# MotionBoard_Rev_C.net
KiCad netlist of a schematic drawn in EAGLE
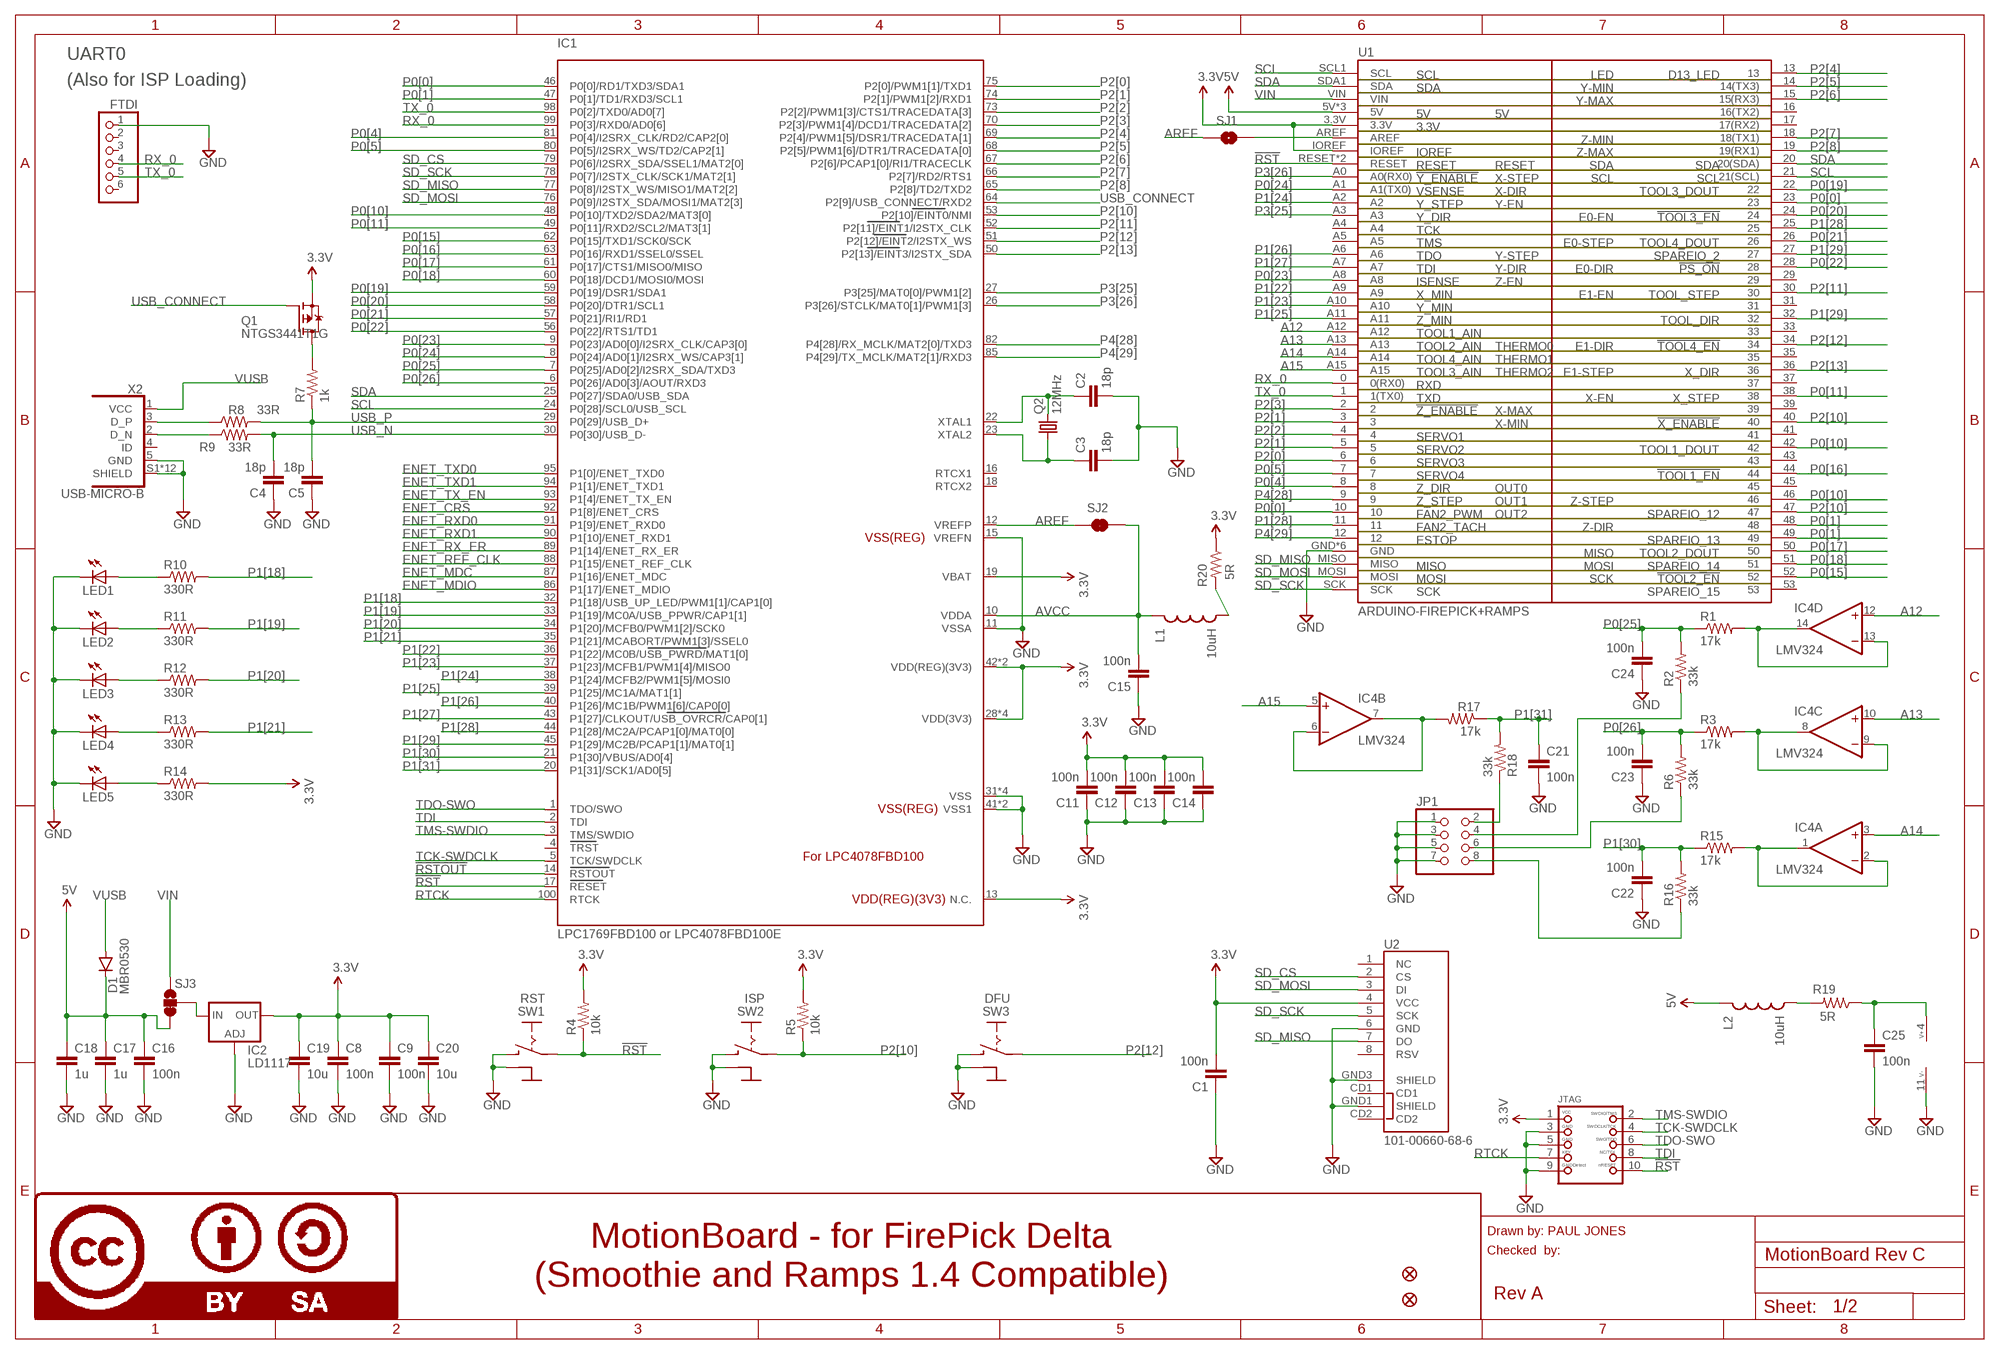
[diagram p0: schematic, sheet 1]
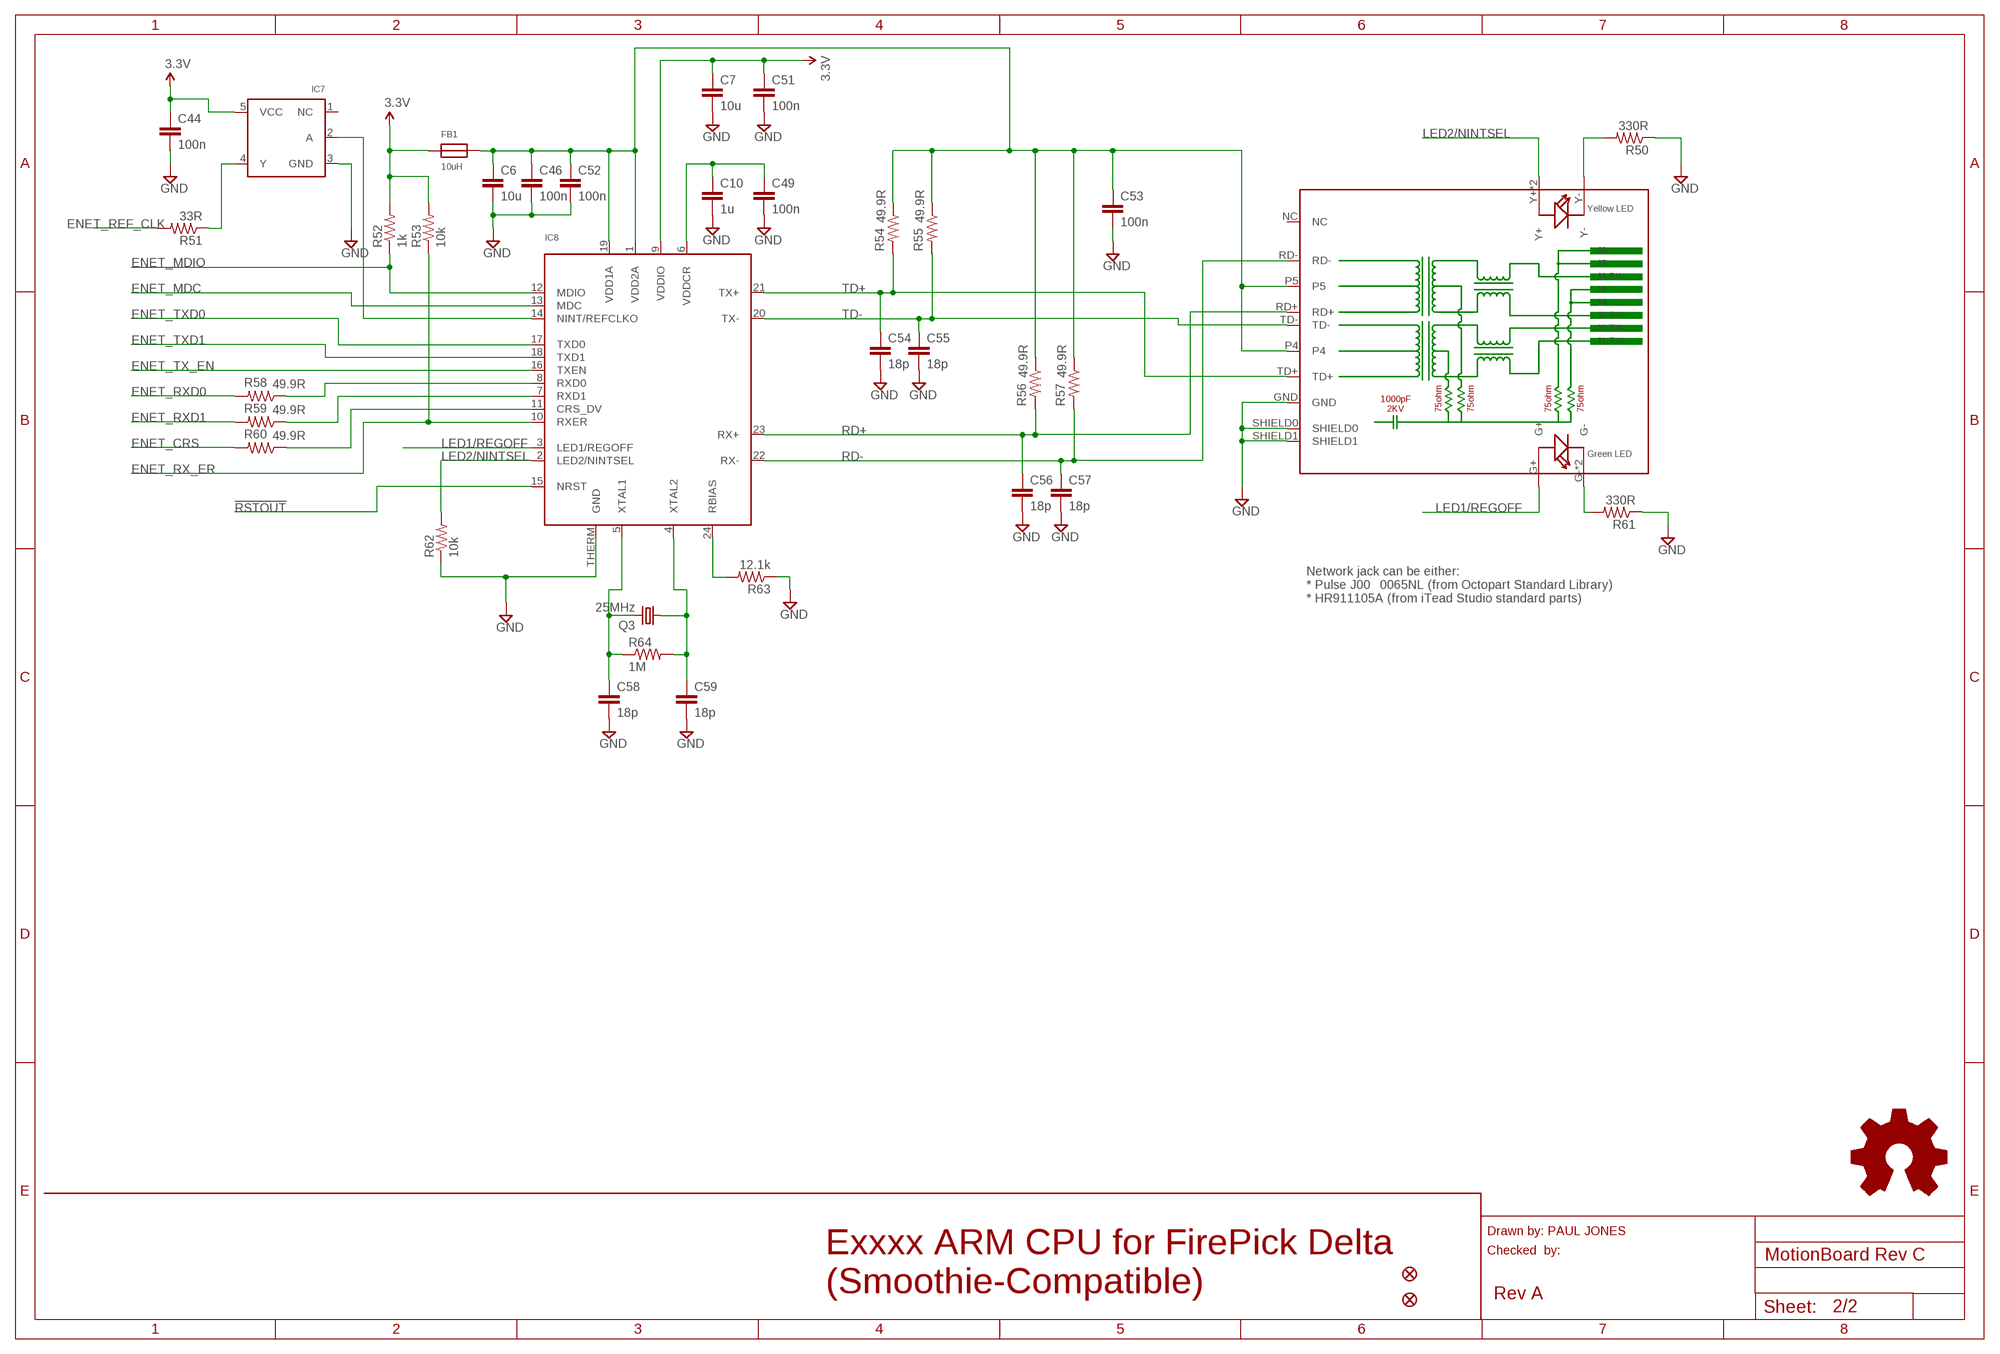
[diagram p1: schematic, sheet 2]

(export (version "E")
  (design (tool "Eeschema 10.0.6"))
  (components
    (comp (ref "C1")
      (value "100n")
      (footprint "eagle-import:0603")
      (libsource (lib "eagle-import") (part "CAP0603"))
    )
    (comp (ref "C2")
      (value "18p")
      (footprint "eagle-import:0603")
      (libsource (lib "eagle-import") (part "CAP0603"))
    )
    (comp (ref "C3")
      (value "18p")
      (footprint "eagle-import:0603")
      (libsource (lib "eagle-import") (part "CAP0603"))
    )
    (comp (ref "C4")
      (value "18p")
      (footprint "eagle-import:0603")
      (libsource (lib "eagle-import") (part "CAP0603"))
    )
    (comp (ref "C5")
      (value "18p")
      (footprint "eagle-import:0603")
      (libsource (lib "eagle-import") (part "CAP0603"))
    )
    (comp (ref "C8")
      (value "100n")
      (footprint "eagle-import:0603")
      (libsource (lib "eagle-import") (part "CAP0603"))
    )
    (comp (ref "C9")
      (value "100n")
      (footprint "eagle-import:0603")
      (libsource (lib "eagle-import") (part "CAP0603"))
    )
    (comp (ref "C11")
      (value "100n")
      (footprint "eagle-import:0603")
      (libsource (lib "eagle-import") (part "CAP0603"))
    )
    (comp (ref "C12")
      (value "100n")
      (footprint "eagle-import:0603")
      (libsource (lib "eagle-import") (part "CAP0603"))
    )
    (comp (ref "C13")
      (value "100n")
      (footprint "eagle-import:0603")
      (libsource (lib "eagle-import") (part "CAP0603"))
    )
    (comp (ref "C14")
      (value "100n")
      (footprint "eagle-import:0603")
      (libsource (lib "eagle-import") (part "CAP0603"))
    )
    (comp (ref "C15")
      (value "100n")
      (footprint "eagle-import:0603")
      (libsource (lib "eagle-import") (part "CAP0603"))
    )
    (comp (ref "C16")
      (value "100n")
      (footprint "eagle-import:0603")
      (libsource (lib "eagle-import") (part "CAP0603"))
    )
    (comp (ref "C17")
      (value "1u")
      (footprint "eagle-import:0603")
      (libsource (lib "eagle-import") (part "CAP0603"))
    )
    (comp (ref "C18")
      (value "1u")
      (footprint "eagle-import:0603")
      (libsource (lib "eagle-import") (part "CAP0603"))
    )
    (comp (ref "C19")
      (value "10u")
      (footprint "eagle-import:0603")
      (libsource (lib "eagle-import") (part "CAP0603"))
    )
    (comp (ref "C20")
      (value "10u")
      (footprint "eagle-import:0603")
      (libsource (lib "eagle-import") (part "CAP0603"))
    )
    (comp (ref "C21")
      (value "100n")
      (footprint "eagle-import:0603")
      (libsource (lib "eagle-import") (part "CAP0603"))
    )
    (comp (ref "C22")
      (value "100n")
      (footprint "eagle-import:0603")
      (libsource (lib "eagle-import") (part "CAP0603"))
    )
    (comp (ref "C23")
      (value "100n")
      (footprint "eagle-import:0603")
      (libsource (lib "eagle-import") (part "CAP0603"))
    )
    (comp (ref "C24")
      (value "100n")
      (footprint "eagle-import:0603")
      (libsource (lib "eagle-import") (part "CAP0603"))
    )
    (comp (ref "C25")
      (value "100n")
      (footprint "eagle-import:0603")
      (libsource (lib "eagle-import") (part "CAP0603"))
    )
    (comp (ref "D1")
      (value "MBR0530")
      (footprint "eagle-import:SOD-123")
      (libsource (lib "eagle-import") (part "DIODESOD123"))
    )
    (comp (ref "DFU")
      (value "SW3")
      (footprint "eagle-import:TOGGLE-SW-SMD")
      (libsource (lib "eagle-import") (part "TOGGLE-SW-SMD"))
    )
    (comp (ref "FID5")
      (value "FIDUCIAL1X2")
      (footprint "eagle-import:FIDUCIAL-1X2")
      (libsource (lib "eagle-import") (part "FIDUCIAL1X2"))
    )
    (comp (ref "FID6")
      (value "FIDUCIAL1X2")
      (footprint "eagle-import:FIDUCIAL-1X2")
      (libsource (lib "eagle-import") (part "FIDUCIAL1X2"))
    )
    (comp (ref "FTDI")
      (value "PINHD-1X6")
      (footprint "eagle-import:1X06")
      (libsource (lib "eagle-import") (part "PINHD-1X6"))
    )
    (comp (ref "IC1")
      (value "LPC1769FBD100 or LPC4078FBD100E")
      (footprint "eagle-import:LQFP100")
      (libsource (lib "eagle-import") (part "LPC1768"))
    )
    (comp (ref "IC2")
      (value "LD1117")
      (footprint "eagle-import:SOT223")
      (libsource (lib "eagle-import") (part "LD117A?S12TR"))
    )
    (comp (ref "IC4")
      (value "LMV324")
      (footprint "eagle-import:SO14")
      (libsource (lib "eagle-import") (part "OPA4743UA"))
    )
    (comp (ref "ISP")
      (value "SW2")
      (footprint "eagle-import:TOGGLE-SW-SMD")
      (libsource (lib "eagle-import") (part "TOGGLE-SW-SMD"))
    )
    (comp (ref "JP1")
      (value "PINHD-2X04_2.54-SMD")
      (footprint "eagle-import:2X04SMD")
      (libsource (lib "eagle-import") (part "PINHD-2X04_2.54-SMD"))
    )
    (comp (ref "JTAG")
      (value "JTAG-CORTEXM3")
      (footprint "eagle-import:2X05_1.27MM_SMT")
      (libsource (lib "eagle-import") (part "JTAG-CORTEXM3"))
    )
    (comp (ref "L1")
      (value "10uH")
      (footprint "eagle-import:0603")
      (libsource (lib "eagle-import") (part "INDUCTOR0603"))
    )
    (comp (ref "L2")
      (value "10uH")
      (footprint "eagle-import:0603")
      (libsource (lib "eagle-import") (part "INDUCTOR0603"))
    )
    (comp (ref "LED1")
      (value "LED")
      (footprint "eagle-import:LED-1206-BOTTOM")
      (libsource (lib "eagle-import") (part "LED"))
    )
    (comp (ref "LED2")
      (value "LED")
      (footprint "eagle-import:LED-1206-BOTTOM")
      (libsource (lib "eagle-import") (part "LED"))
    )
    (comp (ref "LED3")
      (value "LED")
      (footprint "eagle-import:LED-1206-BOTTOM")
      (libsource (lib "eagle-import") (part "LED"))
    )
    (comp (ref "LED4")
      (value "LED")
      (footprint "eagle-import:LED-1206-BOTTOM")
      (libsource (lib "eagle-import") (part "LED"))
    )
    (comp (ref "LED5")
      (value "LED")
      (footprint "eagle-import:LED-1206-BOTTOM")
      (libsource (lib "eagle-import") (part "LED"))
    )
    (comp (ref "LOGO6")
      (value "LOGO-CC-BY-SAMEDIUM")
      (footprint "eagle-import:LOGO-CC-BY-SA-MEDIUM")
      (libsource (lib "eagle-import") (part "LOGO-CC-BY-SAMEDIUM"))
    )
    (comp (ref "Q1")
      (value "NTGS3441T1G")
      (footprint "eagle-import:SC74_INFINEON")
      (libsource (lib "eagle-import") (part "BSL207SP"))
    )
    (comp (ref "Q2")
      (value "12MHz")
      (footprint "eagle-import:HC49UP")
      (libsource (lib "eagle-import") (part "CRYSTALHC49UP"))
    )
    (comp (ref "R1")
      (value "17k")
      (footprint "eagle-import:0603")
      (libsource (lib "eagle-import") (part "RESISTOR0603"))
    )
    (comp (ref "R2")
      (value "33k")
      (footprint "eagle-import:0603")
      (libsource (lib "eagle-import") (part "RESISTOR0603"))
    )
    (comp (ref "R3")
      (value "17k")
      (footprint "eagle-import:0603")
      (libsource (lib "eagle-import") (part "RESISTOR0603"))
    )
    (comp (ref "R4")
      (value "10k")
      (footprint "eagle-import:R0603")
      (libsource (lib "eagle-import") (part "R-US_R0603"))
    )
    (comp (ref "R5")
      (value "10k")
      (footprint "eagle-import:R0603")
      (libsource (lib "eagle-import") (part "R-US_R0603"))
    )
    (comp (ref "R6")
      (value "33k")
      (footprint "eagle-import:0603")
      (libsource (lib "eagle-import") (part "RESISTOR0603"))
    )
    (comp (ref "R7")
      (value "1k")
      (footprint "eagle-import:R0603")
      (libsource (lib "eagle-import") (part "R-US_R0603"))
    )
    (comp (ref "R8")
      (value "33R")
      (footprint "eagle-import:R0603")
      (libsource (lib "eagle-import") (part "R-US_R0603"))
    )
    (comp (ref "R9")
      (value "33R")
      (footprint "eagle-import:R0603")
      (libsource (lib "eagle-import") (part "R-US_R0603"))
    )
    (comp (ref "R10")
      (value "330R")
      (footprint "eagle-import:R0603")
      (libsource (lib "eagle-import") (part "R-US_R0603"))
    )
    (comp (ref "R11")
      (value "330R")
      (footprint "eagle-import:R0603")
      (libsource (lib "eagle-import") (part "R-US_R0603"))
    )
    (comp (ref "R12")
      (value "330R")
      (footprint "eagle-import:R0603")
      (libsource (lib "eagle-import") (part "R-US_R0603"))
    )
    (comp (ref "R13")
      (value "330R")
      (footprint "eagle-import:R0603")
      (libsource (lib "eagle-import") (part "R-US_R0603"))
    )
    (comp (ref "R14")
      (value "330R")
      (footprint "eagle-import:R0603")
      (libsource (lib "eagle-import") (part "R-US_R0603"))
    )
    (comp (ref "R15")
      (value "17k")
      (footprint "eagle-import:0603")
      (libsource (lib "eagle-import") (part "RESISTOR0603"))
    )
    (comp (ref "R16")
      (value "33k")
      (footprint "eagle-import:0603")
      (libsource (lib "eagle-import") (part "RESISTOR0603"))
    )
    (comp (ref "R17")
      (value "17k")
      (footprint "eagle-import:0603")
      (libsource (lib "eagle-import") (part "RESISTOR0603"))
    )
    (comp (ref "R18")
      (value "33k")
      (footprint "eagle-import:0603")
      (libsource (lib "eagle-import") (part "RESISTOR0603"))
    )
    (comp (ref "R19")
      (value "5R")
      (footprint "eagle-import:0603")
      (libsource (lib "eagle-import") (part "RESISTOR0603"))
    )
    (comp (ref "R20")
      (value "5R")
      (footprint "eagle-import:0603")
      (libsource (lib "eagle-import") (part "RESISTOR0603"))
    )
    (comp (ref "RST")
      (value "SW1")
      (footprint "eagle-import:TOGGLE-SW-SMD")
      (libsource (lib "eagle-import") (part "TOGGLE-SW-SMD"))
    )
    (comp (ref "SJ1")
      (value "JUMPER-PAD-2-NOYES_SILK")
      (footprint "eagle-import:PAD-JUMPER-2-NO_YES_SILK")
      (libsource (lib "eagle-import") (part "JUMPER-PAD-2-NOYES_SILK"))
    )
    (comp (ref "SJ2")
      (value "JUMPER-PAD-2-NC_BY_TRACE")
      (footprint "eagle-import:PAD-JUMPER-2-NC_BY_TRACE_YES_SILK")
      (libsource (lib "eagle-import") (part "JUMPER-PAD-2-NC_BY_TRACE"))
    )
    (comp (ref "SJ3")
      (value "JUMPER-PAD-3-2OF3_NC_BY_TRACE_SMALL")
      (footprint "eagle-import:PAD-JUMPER-3-2OF3_NC_BY_TRACE_YES_SILK_FULL_BOX")
      (libsource (lib "eagle-import") (part "JUMPER-PAD-3-2OF3_NC_BY_TRACE_SMALL"))
    )
    (comp (ref "U1")
      (value "ARDUINO-FIREPICK+RAMPS")
      (footprint "eagle-import:ARDUINO_MEGA_NEW")
      (libsource (lib "eagle-import") (part "ARDUINO-FIREPICK+RAMPS"))
    )
    (comp (ref "U2")
      (value "101-00660-68-6")
      (footprint "eagle-import:MICRO-SD-SOCKET-PP")
      (libsource (lib "eagle-import") (part "USD-SOCKETNEW"))
    )
    (comp (ref "X2")
      (value "USB-MICRO-B")
      (footprint "eagle-import:FCI-10118194-0001LF")
      (libsource (lib "eagle-import") (part "USB-MICRO-B"))
    )
    (comp (ref "C6")
      (value "10u")
      (footprint "eagle-import:0603")
      (libsource (lib "eagle-import") (part "CAP0603"))
    )
    (comp (ref "C7")
      (value "10u")
      (footprint "eagle-import:0603")
      (libsource (lib "eagle-import") (part "CAP0603"))
    )
    (comp (ref "C10")
      (value "1u")
      (footprint "eagle-import:0603")
      (libsource (lib "eagle-import") (part "CAP0603"))
    )
    (comp (ref "C44")
      (value "100n")
      (footprint "eagle-import:0603")
      (libsource (lib "eagle-import") (part "CAP0603"))
    )
    (comp (ref "C46")
      (value "100n")
      (footprint "eagle-import:0603")
      (libsource (lib "eagle-import") (part "CAP0603"))
    )
    (comp (ref "C49")
      (value "100n")
      (footprint "eagle-import:0603")
      (libsource (lib "eagle-import") (part "CAP0603"))
    )
    (comp (ref "C51")
      (value "100n")
      (footprint "eagle-import:0603")
      (libsource (lib "eagle-import") (part "CAP0603"))
    )
    (comp (ref "C52")
      (value "100n")
      (footprint "eagle-import:0603")
      (libsource (lib "eagle-import") (part "CAP0603"))
    )
    (comp (ref "C53")
      (value "100n")
      (footprint "eagle-import:0603")
      (libsource (lib "eagle-import") (part "CAP0603"))
    )
    (comp (ref "C54")
      (value "18p")
      (footprint "eagle-import:0603")
      (libsource (lib "eagle-import") (part "CAP0603"))
    )
    (comp (ref "C55")
      (value "18p")
      (footprint "eagle-import:0603")
      (libsource (lib "eagle-import") (part "CAP0603"))
    )
    (comp (ref "C56")
      (value "18p")
      (footprint "eagle-import:0603")
      (libsource (lib "eagle-import") (part "CAP0603"))
    )
    (comp (ref "C57")
      (value "18p")
      (footprint "eagle-import:0603")
      (libsource (lib "eagle-import") (part "CAP0603"))
    )
    (comp (ref "C58")
      (value "18p")
      (footprint "eagle-import:0603")
      (libsource (lib "eagle-import") (part "CAP0603"))
    )
    (comp (ref "C59")
      (value "18p")
      (footprint "eagle-import:0603")
      (libsource (lib "eagle-import") (part "CAP0603"))
    )
    (comp (ref "FB1")
      (value "10uH")
      (footprint "eagle-import:0603")
      (libsource (lib "eagle-import") (part "FERRITE"))
    )
    (comp (ref "FID17")
      (value "FIDUCIAL1X2")
      (footprint "eagle-import:FIDUCIAL-1X2")
      (libsource (lib "eagle-import") (part "FIDUCIAL1X2"))
    )
    (comp (ref "FID18")
      (value "FIDUCIAL1X2")
      (footprint "eagle-import:FIDUCIAL-1X2")
      (libsource (lib "eagle-import") (part "FIDUCIAL1X2"))
    )
    (comp (ref "IC7")
      (value "74LVC1G04")
      (footprint "eagle-import:SOT23-5")
      (libsource (lib "eagle-import") (part "74LVC1G04"))
    )
    (comp (ref "IC8")
      (value "LAN8720")
      (footprint "eagle-import:QFN24_4MM")
      (libsource (lib "eagle-import") (part "LAN8720"))
    )
    (comp (ref "LOGO10")
      (value "LOGO-OSHWSMALL")
      (footprint "eagle-import:LOGO-OSHW-SMALL")
      (libsource (lib "eagle-import") (part "LOGO-OSHWSMALL"))
    )
    (comp (ref "Q3")
      (value "25MHz")
      (footprint "eagle-import:HC49UP")
      (libsource (lib "eagle-import") (part "CRYSTALHC49UP"))
    )
    (comp (ref "R50")
      (value "330R")
      (footprint "eagle-import:R0603")
      (libsource (lib "eagle-import") (part "R-US_R0603"))
    )
    (comp (ref "R51")
      (value "33R")
      (footprint "eagle-import:R0603")
      (libsource (lib "eagle-import") (part "R-US_R0603"))
    )
    (comp (ref "R52")
      (value "1k")
      (footprint "eagle-import:R0603")
      (libsource (lib "eagle-import") (part "R-US_R0603"))
    )
    (comp (ref "R53")
      (value "10k")
      (footprint "eagle-import:R0603")
      (libsource (lib "eagle-import") (part "R-US_R0603"))
    )
    (comp (ref "R54")
      (value "49.9R")
      (footprint "eagle-import:R0603")
      (libsource (lib "eagle-import") (part "R-US_R0603"))
    )
    (comp (ref "R55")
      (value "49.9R")
      (footprint "eagle-import:R0603")
      (libsource (lib "eagle-import") (part "R-US_R0603"))
    )
    (comp (ref "R56")
      (value "49.9R")
      (footprint "eagle-import:R0603")
      (libsource (lib "eagle-import") (part "R-US_R0603"))
    )
    (comp (ref "R57")
      (value "49.9R")
      (footprint "eagle-import:R0603")
      (libsource (lib "eagle-import") (part "R-US_R0603"))
    )
    (comp (ref "R58")
      (value "49.9R")
      (footprint "eagle-import:R0603")
      (libsource (lib "eagle-import") (part "R-US_R0603"))
    )
    (comp (ref "R59")
      (value "49.9R")
      (footprint "eagle-import:R0603")
      (libsource (lib "eagle-import") (part "R-US_R0603"))
    )
    (comp (ref "R60")
      (value "49.9R")
      (footprint "eagle-import:R0603")
      (libsource (lib "eagle-import") (part "R-US_R0603"))
    )
    (comp (ref "R61")
      (value "330R")
      (footprint "eagle-import:R0603")
      (libsource (lib "eagle-import") (part "R-US_R0603"))
    )
    (comp (ref "R62")
      (value "10k")
      (footprint "eagle-import:R0603")
      (libsource (lib "eagle-import") (part "R-US_R0603"))
    )
    (comp (ref "R63")
      (value "12.1k")
      (footprint "eagle-import:R0603")
      (libsource (lib "eagle-import") (part "R-US_R0603"))
    )
    (comp (ref "R64")
      (value "1M")
      (footprint "eagle-import:R0603")
      (libsource (lib "eagle-import") (part "R-US_R0603"))
    )
    (comp (ref "RJ1")
      (value "HR911105A")
      (footprint "eagle-import:HR911105A")
      (libsource (lib "eagle-import") (part "HR911105A"))
    )
  )
  (nets
    (net (code "1") (name "3.3V") (class "Default")
      (node (ref "C1") (pin "2") (pinfunction "2_2") (pintype "passive"))
      (node (ref "C11") (pin "2") (pinfunction "2_2") (pintype "passive"))
      (node (ref "C12") (pin "2") (pinfunction "2_2") (pintype "passive"))
      (node (ref "C13") (pin "2") (pinfunction "2_2") (pintype "passive"))
      (node (ref "C14") (pin "2") (pinfunction "2_2") (pintype "passive"))
      (node (ref "C19") (pin "1") (pinfunction "1_1") (pintype "passive"))
      (node (ref "C20") (pin "1") (pinfunction "1_1") (pintype "passive"))
      (node (ref "C44") (pin "1") (pinfunction "1_1") (pintype "passive"))
      (node (ref "C51") (pin "1") (pinfunction "1_1") (pintype "passive"))
      (node (ref "C7") (pin "1") (pinfunction "1_1") (pintype "passive"))
      (node (ref "C8") (pin "1") (pinfunction "1_1") (pintype "passive"))
      (node (ref "C9") (pin "1") (pinfunction "1_1") (pintype "passive"))
      (node (ref "FB1") (pin "1") (pinfunction "P$1_1") (pintype "bidirectional"))
      (node (ref "IC1") (pin "13") (pinfunction "N.C._13") (pintype "bidirectional"))
      (node (ref "IC1") (pin "19") (pinfunction "VBAT_19") (pintype "bidirectional"))
      (node (ref "IC1") (pin "28") (pinfunction "VDD(3V3)_28") (pintype "bidirectional"))
      (node (ref "IC1") (pin "42") (pinfunction "VDD(REG)(3V3)_42") (pintype "bidirectional"))
      (node (ref "IC1") (pin "54") (pinfunction "VDD(3V3)_54") (pintype "bidirectional"))
      (node (ref "IC1") (pin "71") (pinfunction "VDD(3V3)_71") (pintype "bidirectional"))
      (node (ref "IC1") (pin "84") (pinfunction "VDD(REG)(3V3)_84") (pintype "bidirectional"))
      (node (ref "IC1") (pin "96") (pinfunction "VDD(3V3)_96") (pintype "bidirectional"))
      (node (ref "IC2") (pin "4") (pinfunction "OUT_4") (pintype "passive"))
      (node (ref "IC7") (pin "5") (pinfunction "VCC_5") (pintype "power_in"))
      (node (ref "IC8") (pin "9") (pinfunction "VDDIO_9") (pintype "bidirectional"))
      (node (ref "JTAG") (pin "1") (pinfunction "1_1") (pintype "passive"))
      (node (ref "Q1") (pin "4") (pinfunction "S_4") (pintype "passive"))
      (node (ref "R14") (pin "2") (pinfunction "2_2") (pintype "passive"))
      (node (ref "R20") (pin "1") (pinfunction "1_1") (pintype "passive"))
      (node (ref "R4") (pin "2") (pinfunction "2_2") (pintype "passive"))
      (node (ref "R5") (pin "2") (pinfunction "2_2") (pintype "passive"))
      (node (ref "R52") (pin "2") (pinfunction "2_2") (pintype "passive"))
      (node (ref "R53") (pin "2") (pinfunction "2_2") (pintype "passive"))
      (node (ref "U1") (pin "3.3V") (pinfunction "3.3V_3.3V") (pintype "bidirectional"))
      (node (ref "U1") (pin "IOREF") (pinfunction "IOREF_IOREF") (pintype "bidirectional"))
      (node (ref "U2") (pin "4") (pinfunction "VCC_4") (pintype "bidirectional"))
    )
    (net (code "2") (name "5V") (class "Default")
      (node (ref "C16") (pin "1") (pinfunction "1_1") (pintype "passive"))
      (node (ref "C17") (pin "1") (pinfunction "1_1") (pintype "passive"))
      (node (ref "C18") (pin "1") (pinfunction "1_1") (pintype "passive"))
      (node (ref "D1") (pin "C") (pinfunction "C_C") (pintype "passive"))
      (node (ref "L2") (pin "1") (pinfunction "1_1") (pintype "passive"))
      (node (ref "SJ3") (pin "3") (pinfunction "3_3") (pintype "passive"))
      (node (ref "U1") (pin "5V") (pinfunction "5V_5V") (pintype "bidirectional"))
      (node (ref "U1") (pin "5V@1") (pinfunction "5V_5V@1") (pintype "bidirectional"))
      (node (ref "U1") (pin "5V@2") (pinfunction "5V_5V@2") (pintype "bidirectional"))
    )
    (net (code "3") (name "A12") (class "Default")
      (node (ref "IC4") (pin "12") (pinfunction "+IN_12") (pintype "input"))
      (node (ref "U1") (pin "A12") (pinfunction "A12_A12") (pintype "bidirectional"))
    )
    (net (code "4") (name "A13") (class "Default")
      (node (ref "IC4") (pin "10") (pinfunction "+IN_10") (pintype "input"))
      (node (ref "U1") (pin "A13") (pinfunction "A13_A13") (pintype "bidirectional"))
    )
    (net (code "5") (name "A14") (class "Default")
      (node (ref "IC4") (pin "3") (pinfunction "+IN_3") (pintype "input"))
      (node (ref "U1") (pin "A14") (pinfunction "A14_A14") (pintype "bidirectional"))
    )
    (net (code "6") (name "A15") (class "Default")
      (node (ref "IC4") (pin "5") (pinfunction "+IN_5") (pintype "input"))
      (node (ref "U1") (pin "A15") (pinfunction "A15_A15") (pintype "bidirectional"))
    )
    (net (code "7") (name "AREF") (class "Default")
      (node (ref "IC1") (pin "12") (pinfunction "VREFP_12") (pintype "bidirectional"))
      (node (ref "SJ1") (pin "1") (pinfunction "1_1") (pintype "passive"))
      (node (ref "SJ2") (pin "1") (pinfunction "1_1") (pintype "passive"))
    )
    (net (code "8") (name "AVCC") (class "Default")
      (node (ref "C15") (pin "2") (pinfunction "2_2") (pintype "passive"))
      (node (ref "IC1") (pin "10") (pinfunction "VDDA_10") (pintype "bidirectional"))
      (node (ref "L1") (pin "1") (pinfunction "1_1") (pintype "passive"))
      (node (ref "SJ2") (pin "2") (pinfunction "2_2") (pintype "passive"))
    )
    (net (code "9") (name "ENET_CRS") (class "Default")
      (node (ref "IC1") (pin "92") (pinfunction "P1[8]/ENET_CRS_92") (pintype "bidirectional"))
      (node (ref "R60") (pin "2") (pinfunction "2_2") (pintype "passive"))
    )
    (net (code "10") (name "ENET_MDC") (class "Default")
      (node (ref "IC1") (pin "87") (pinfunction "P1[16]/ENET_MDC_87") (pintype "bidirectional"))
      (node (ref "IC8") (pin "13") (pinfunction "MDC_13") (pintype "bidirectional"))
    )
    (net (code "11") (name "ENET_MDIO") (class "Default")
      (node (ref "IC1") (pin "86") (pinfunction "P1[17]/ENET_MDIO_86") (pintype "bidirectional"))
      (node (ref "IC8") (pin "12") (pinfunction "MDIO_12") (pintype "bidirectional"))
      (node (ref "R52") (pin "1") (pinfunction "1_1") (pintype "passive"))
    )
    (net (code "12") (name "ENET_REF_CLK") (class "Default")
      (node (ref "IC1") (pin "88") (pinfunction "P1[15]/ENET_REF_CLK_88") (pintype "bidirectional"))
      (node (ref "R51") (pin "2") (pinfunction "2_2") (pintype "passive"))
    )
    (net (code "13") (name "ENET_RXD0") (class "Default")
      (node (ref "IC1") (pin "91") (pinfunction "P1[9]/ENET_RXD0_91") (pintype "bidirectional"))
      (node (ref "R58") (pin "2") (pinfunction "2_2") (pintype "passive"))
    )
    (net (code "14") (name "ENET_RXD1") (class "Default")
      (node (ref "IC1") (pin "90") (pinfunction "P1[10]/ENET_RXD1_90") (pintype "bidirectional"))
      (node (ref "R59") (pin "2") (pinfunction "2_2") (pintype "passive"))
    )
    (net (code "15") (name "ENET_RX_ER") (class "Default")
      (node (ref "IC1") (pin "89") (pinfunction "P1[14]/ENET_RX_ER_89") (pintype "bidirectional"))
      (node (ref "IC8") (pin "10") (pinfunction "RXER_10") (pintype "bidirectional"))
      (node (ref "R53") (pin "1") (pinfunction "1_1") (pintype "passive"))
    )
    (net (code "16") (name "ENET_TXD0") (class "Default")
      (node (ref "IC1") (pin "95") (pinfunction "P1[0]/ENET_TXD0_95") (pintype "bidirectional"))
      (node (ref "IC8") (pin "17") (pinfunction "TXD0_17") (pintype "bidirectional"))
    )
    (net (code "17") (name "ENET_TXD1") (class "Default")
      (node (ref "IC1") (pin "94") (pinfunction "P1[1]/ENET_TXD1_94") (pintype "bidirectional"))
      (node (ref "IC8") (pin "18") (pinfunction "TXD1_18") (pintype "bidirectional"))
    )
    (net (code "18") (name "ENET_TX_EN") (class "Default")
      (node (ref "IC1") (pin "93") (pinfunction "P1[4]/ENET_TX_EN_93") (pintype "bidirectional"))
      (node (ref "IC8") (pin "16") (pinfunction "TXEN_16") (pintype "bidirectional"))
    )
    (net (code "19") (name "GND") (class "Default")
      (node (ref "C1") (pin "1") (pinfunction "1_1") (pintype "passive"))
      (node (ref "C10") (pin "2") (pinfunction "2_2") (pintype "passive"))
      (node (ref "C11") (pin "1") (pinfunction "1_1") (pintype "passive"))
      (node (ref "C12") (pin "1") (pinfunction "1_1") (pintype "passive"))
      (node (ref "C13") (pin "1") (pinfunction "1_1") (pintype "passive"))
      (node (ref "C14") (pin "1") (pinfunction "1_1") (pintype "passive"))
      (node (ref "C15") (pin "1") (pinfunction "1_1") (pintype "passive"))
      (node (ref "C16") (pin "2") (pinfunction "2_2") (pintype "passive"))
      (node (ref "C17") (pin "2") (pinfunction "2_2") (pintype "passive"))
      (node (ref "C18") (pin "2") (pinfunction "2_2") (pintype "passive"))
      (node (ref "C19") (pin "2") (pinfunction "2_2") (pintype "passive"))
      (node (ref "C2") (pin "2") (pinfunction "2_2") (pintype "passive"))
      (node (ref "C20") (pin "2") (pinfunction "2_2") (pintype "passive"))
      (node (ref "C21") (pin "2") (pinfunction "2_2") (pintype "passive"))
      (node (ref "C22") (pin "1") (pinfunction "1_1") (pintype "passive"))
      (node (ref "C23") (pin "1") (pinfunction "1_1") (pintype "passive"))
      (node (ref "C24") (pin "1") (pinfunction "1_1") (pintype "passive"))
      (node (ref "C25") (pin "2") (pinfunction "2_2") (pintype "passive"))
      (node (ref "C3") (pin "2") (pinfunction "2_2") (pintype "passive"))
      (node (ref "C4") (pin "1") (pinfunction "1_1") (pintype "passive"))
      (node (ref "C44") (pin "2") (pinfunction "2_2") (pintype "passive"))
      (node (ref "C46") (pin "2") (pinfunction "2_2") (pintype "passive"))
      (node (ref "C49") (pin "2") (pinfunction "2_2") (pintype "passive"))
      (node (ref "C5") (pin "1") (pinfunction "1_1") (pintype "passive"))
      (node (ref "C51") (pin "2") (pinfunction "2_2") (pintype "passive"))
      (node (ref "C52") (pin "2") (pinfunction "2_2") (pintype "passive"))
      (node (ref "C53") (pin "2") (pinfunction "2_2") (pintype "passive"))
      (node (ref "C54") (pin "2") (pinfunction "2_2") (pintype "passive"))
      (node (ref "C55") (pin "2") (pinfunction "2_2") (pintype "passive"))
      (node (ref "C56") (pin "2") (pinfunction "2_2") (pintype "passive"))
      (node (ref "C57") (pin "2") (pinfunction "2_2") (pintype "passive"))
      (node (ref "C58") (pin "2") (pinfunction "2_2") (pintype "passive"))
      (node (ref "C59") (pin "2") (pinfunction "2_2") (pintype "passive"))
      (node (ref "C6") (pin "2") (pinfunction "2_2") (pintype "passive"))
      (node (ref "C7") (pin "2") (pinfunction "2_2") (pintype "passive"))
      (node (ref "C8") (pin "2") (pinfunction "2_2") (pintype "passive"))
      (node (ref "C9") (pin "2") (pinfunction "2_2") (pintype "passive"))
      (node (ref "DFU") (pin "1") (pinfunction "C_1") (pintype "passive"))
      (node (ref "DFU") (pin "2") (pinfunction "C_2") (pintype "passive"))
      (node (ref "DFU") (pin "GND") (pinfunction "GND_GND") (pintype "passive"))
      (node (ref "FTDI") (pin "1") (pinfunction "1_1") (pintype "passive"))
      (node (ref "IC1") (pin "11") (pinfunction "VSSA_11") (pintype "bidirectional"))
      (node (ref "IC1") (pin "15") (pinfunction "VREFN_15") (pintype "bidirectional"))
      (node (ref "IC1") (pin "31") (pinfunction "VSS_31") (pintype "bidirectional"))
      (node (ref "IC1") (pin "41") (pinfunction "VSS1_41") (pintype "bidirectional"))
      (node (ref "IC1") (pin "55") (pinfunction "VSS_55") (pintype "bidirectional"))
      (node (ref "IC1") (pin "72") (pinfunction "VSS_72") (pintype "bidirectional"))
      (node (ref "IC1") (pin "83") (pinfunction "VSS1_83") (pintype "bidirectional"))
      (node (ref "IC1") (pin "97") (pinfunction "VSS_97") (pintype "bidirectional"))
      (node (ref "IC2") (pin "1") (pinfunction "ADJ_1") (pintype "input"))
      (node (ref "IC4") (pin "11") (pinfunction "V-_11") (pintype "power_in"))
      (node (ref "IC7") (pin "3") (pinfunction "GND_3") (pintype "power_in"))
      (node (ref "IC8") (pin "THERM") (pinfunction "GND_THERM") (pintype "bidirectional"))
      (node (ref "ISP") (pin "1") (pinfunction "C_1") (pintype "passive"))
      (node (ref "ISP") (pin "2") (pinfunction "C_2") (pintype "passive"))
      (node (ref "ISP") (pin "GND") (pinfunction "GND_GND") (pintype "passive"))
      (node (ref "JP1") (pin "1") (pinfunction "1_1") (pintype "passive"))
      (node (ref "JP1") (pin "3") (pinfunction "3_3") (pintype "passive"))
      (node (ref "JP1") (pin "5") (pinfunction "5_5") (pintype "passive"))
      (node (ref "JP1") (pin "7") (pinfunction "7_7") (pintype "passive"))
      (node (ref "JTAG") (pin "3") (pinfunction "3_3") (pintype "passive"))
      (node (ref "JTAG") (pin "5") (pinfunction "5_5") (pintype "passive"))
      (node (ref "JTAG") (pin "9") (pinfunction "9_9") (pintype "passive"))
      (node (ref "LED1") (pin "C") (pinfunction "C_C") (pintype "passive"))
      (node (ref "LED2") (pin "C") (pinfunction "C_C") (pintype "passive"))
      (node (ref "LED3") (pin "C") (pinfunction "C_C") (pintype "passive"))
      (node (ref "LED4") (pin "C") (pinfunction "C_C") (pintype "passive"))
      (node (ref "LED5") (pin "C") (pinfunction "C_C") (pintype "passive"))
      (node (ref "R50") (pin "1") (pinfunction "1_1") (pintype "passive"))
      (node (ref "R61") (pin "1") (pinfunction "1_1") (pintype "passive"))
      (node (ref "R62") (pin "1") (pinfunction "1_1") (pintype "passive"))
      (node (ref "R63") (pin "1") (pinfunction "1_1") (pintype "passive"))
      (node (ref "RJ1") (pin "GND") (pinfunction "GND_GND") (pintype "bidirectional"))
      (node (ref "RJ1") (pin "SHIELD0") (pinfunction "SHIELD0_SHIELD0") (pintype "bidirectional"))
      (node (ref "RJ1") (pin "SHIELD1") (pinfunction "SHIELD1_SHIELD1") (pintype "bidirectional"))
      (node (ref "RST") (pin "1") (pinfunction "C_1") (pintype "passive"))
      (node (ref "RST") (pin "2") (pinfunction "C_2") (pintype "passive"))
      (node (ref "RST") (pin "GND") (pinfunction "GND_GND") (pintype "passive"))
      (node (ref "U1") (pin "GND") (pinfunction "GND_GND") (pintype "bidirectional"))
      (node (ref "U1") (pin "GND@0") (pinfunction "GND_GND@0") (pintype "bidirectional"))
      (node (ref "U1") (pin "GND@1") (pinfunction "GND_GND@1") (pintype "bidirectional"))
      (node (ref "U1") (pin "GND@2") (pinfunction "GND_GND@2") (pintype "bidirectional"))
      (node (ref "U1") (pin "GND@3") (pinfunction "GND_GND@3") (pintype "bidirectional"))
      (node (ref "U1") (pin "GNDI") (pinfunction "GND_GNDI") (pintype "bidirectional"))
      (node (ref "U2") (pin "6") (pinfunction "GND_6") (pintype "bidirectional"))
      (node (ref "U2") (pin "GND1") (pinfunction "SHIELD_GND1") (pintype "bidirectional"))
      (node (ref "U2") (pin "GND3") (pinfunction "SHIELD_GND3") (pintype "bidirectional"))
      (node (ref "X2") (pin "5") (pinfunction "GND_5") (pintype "bidirectional"))
      (node (ref "X2") (pin "S1") (pinfunction "SHIELD_S1") (pintype "bidirectional"))
      (node (ref "X2") (pin "S10") (pinfunction "SHIELD_S10") (pintype "bidirectional"))
      (node (ref "X2") (pin "S11") (pinfunction "SHIELD_S11") (pintype "bidirectional"))
      (node (ref "X2") (pin "S12") (pinfunction "SHIELD_S12") (pintype "bidirectional"))
      (node (ref "X2") (pin "S2") (pinfunction "SHIELD_S2") (pintype "bidirectional"))
      (node (ref "X2") (pin "S3") (pinfunction "SHIELD_S3") (pintype "bidirectional"))
      (node (ref "X2") (pin "S4") (pinfunction "SHIELD_S4") (pintype "bidirectional"))
      (node (ref "X2") (pin "S5") (pinfunction "SHIELD_S5") (pintype "bidirectional"))
      (node (ref "X2") (pin "S6") (pinfunction "SHIELD_S6") (pintype "bidirectional"))
      (node (ref "X2") (pin "S7") (pinfunction "SHIELD_S7") (pintype "bidirectional"))
      (node (ref "X2") (pin "S8") (pinfunction "SHIELD_S8") (pintype "bidirectional"))
      (node (ref "X2") (pin "S9") (pinfunction "SHIELD_S9") (pintype "bidirectional"))
    )
    (net (code "20") (name "LED1{slash}REGOFF") (class "Default")
      (node (ref "IC8") (pin "3") (pinfunction "LED1/REGOFF_3") (pintype "bidirectional"))
      (node (ref "RJ1") (pin "G+") (pinfunction "G+_G+") (pintype "bidirectional"))
    )
    (net (code "21") (name "LED2{slash}NINTSEL") (class "Default")
      (node (ref "IC8") (pin "2") (pinfunction "LED2/NINTSEL_2") (pintype "bidirectional"))
      (node (ref "R62") (pin "2") (pinfunction "2_2") (pintype "passive"))
      (node (ref "RJ1") (pin "Y+") (pinfunction "Y+_Y+") (pintype "bidirectional"))
      (node (ref "RJ1") (pin "Y++") (pinfunction "Y+_Y++") (pintype "bidirectional"))
    )
    (net (code "22") (name "Net-(FB1-P$2)") (class "Default")
      (node (ref "C46") (pin "1") (pinfunction "1_1") (pintype "passive"))
      (node (ref "C52") (pin "1") (pinfunction "1_1") (pintype "passive"))
      (node (ref "C53") (pin "1") (pinfunction "1_1") (pintype "passive"))
      (node (ref "C6") (pin "1") (pinfunction "1_1") (pintype "passive"))
      (node (ref "FB1") (pin "2") (pinfunction "P$2_2") (pintype "bidirectional"))
      (node (ref "IC8") (pin "1") (pinfunction "VDD2A_1") (pintype "bidirectional"))
      (node (ref "IC8") (pin "19") (pinfunction "VDD1A_19") (pintype "bidirectional"))
      (node (ref "R54") (pin "1") (pinfunction "1_1") (pintype "passive"))
      (node (ref "R55") (pin "1") (pinfunction "1_1") (pintype "passive"))
      (node (ref "R56") (pin "1") (pinfunction "1_1") (pintype "passive"))
      (node (ref "R57") (pin "1") (pinfunction "1_1") (pintype "passive"))
      (node (ref "RJ1") (pin "P4") (pinfunction "P4_P4") (pintype "bidirectional"))
      (node (ref "RJ1") (pin "P5") (pinfunction "P5_P5") (pintype "bidirectional"))
    )
    (net (code "23") (name "Net-(IC1-XTAL1)") (class "Default")
      (node (ref "C2") (pin "1") (pinfunction "1_1") (pintype "passive"))
      (node (ref "IC1") (pin "22") (pinfunction "XTAL1_22") (pintype "bidirectional"))
      (node (ref "Q2") (pin "2") (pinfunction "2_2") (pintype "passive"))
    )
    (net (code "24") (name "Net-(IC1-XTAL2)") (class "Default")
      (node (ref "C3") (pin "1") (pinfunction "1_1") (pintype "passive"))
      (node (ref "IC1") (pin "23") (pinfunction "XTAL2_23") (pintype "bidirectional"))
      (node (ref "Q2") (pin "1") (pinfunction "1_1") (pintype "passive"))
    )
    (net (code "25") (name "Net-(IC2-IN)") (class "Default")
      (node (ref "IC2") (pin "3") (pinfunction "IN_3") (pintype "input"))
      (node (ref "SJ3") (pin "2") (pinfunction "2_2") (pintype "passive"))
    )
    (net (code "26") (name "Net-(IC4A--IN)") (class "Default")
      (node (ref "IC4") (pin "1") (pinfunction "OUT_1") (pintype "output"))
      (node (ref "IC4") (pin "2") (pinfunction "-IN_2") (pintype "input"))
      (node (ref "R15") (pin "2") (pinfunction "2_2") (pintype "passive"))
    )
    (net (code "27") (name "Net-(IC4B--IN)") (class "Default")
      (node (ref "IC4") (pin "6") (pinfunction "-IN_6") (pintype "input"))
      (node (ref "IC4") (pin "7") (pinfunction "OUT_7") (pintype "output"))
      (node (ref "R17") (pin "2") (pinfunction "2_2") (pintype "passive"))
    )
    (net (code "28") (name "Net-(IC4C--IN)") (class "Default")
      (node (ref "IC4") (pin "8") (pinfunction "OUT_8") (pintype "output"))
      (node (ref "IC4") (pin "9") (pinfunction "-IN_9") (pintype "input"))
      (node (ref "R3") (pin "2") (pinfunction "2_2") (pintype "passive"))
    )
    (net (code "29") (name "Net-(IC4D--IN)") (class "Default")
      (node (ref "IC4") (pin "13") (pinfunction "-IN_13") (pintype "input"))
      (node (ref "IC4") (pin "14") (pinfunction "OUT_14") (pintype "output"))
      (node (ref "R1") (pin "2") (pinfunction "2_2") (pintype "passive"))
    )
    (net (code "30") (name "Net-(IC4E-V+)") (class "Default")
      (node (ref "C25") (pin "1") (pinfunction "1_1") (pintype "passive"))
      (node (ref "IC4") (pin "4") (pinfunction "V+_4") (pintype "power_in"))
      (node (ref "R19") (pin "1") (pinfunction "1_1") (pintype "passive"))
    )
    (net (code "31") (name "Net-(IC7-A)") (class "Default")
      (node (ref "IC7") (pin "2") (pinfunction "A_2") (pintype "bidirectional"))
      (node (ref "IC8") (pin "14") (pinfunction "NINT/REFCLKO_14") (pintype "bidirectional"))
    )
    (net (code "32") (name "Net-(IC7-Y)") (class "Default")
      (node (ref "IC7") (pin "4") (pinfunction "Y_4") (pintype "bidirectional"))
      (node (ref "R51") (pin "1") (pinfunction "1_1") (pintype "passive"))
    )
    (net (code "33") (name "Net-(IC8-CRS_DV)") (class "Default")
      (node (ref "IC8") (pin "11") (pinfunction "CRS_DV_11") (pintype "bidirectional"))
      (node (ref "R60") (pin "1") (pinfunction "1_1") (pintype "passive"))
    )
    (net (code "34") (name "Net-(IC8-RBIAS)") (class "Default")
      (node (ref "IC8") (pin "24") (pinfunction "RBIAS_24") (pintype "bidirectional"))
      (node (ref "R63") (pin "2") (pinfunction "2_2") (pintype "passive"))
    )
    (net (code "35") (name "Net-(IC8-RXD0)") (class "Default")
      (node (ref "IC8") (pin "8") (pinfunction "RXD0_8") (pintype "bidirectional"))
      (node (ref "R58") (pin "1") (pinfunction "1_1") (pintype "passive"))
    )
    (net (code "36") (name "Net-(IC8-RXD1)") (class "Default")
      (node (ref "IC8") (pin "7") (pinfunction "RXD1_7") (pintype "bidirectional"))
      (node (ref "R59") (pin "1") (pinfunction "1_1") (pintype "passive"))
    )
    (net (code "37") (name "Net-(IC8-VDDCR)") (class "Default")
      (node (ref "C10") (pin "1") (pinfunction "1_1") (pintype "passive"))
      (node (ref "C49") (pin "1") (pinfunction "1_1") (pintype "passive"))
      (node (ref "IC8") (pin "6") (pinfunction "VDDCR_6") (pintype "bidirectional"))
    )
    (net (code "38") (name "Net-(IC8-XTAL1)") (class "Default")
      (node (ref "C58") (pin "1") (pinfunction "1_1") (pintype "passive"))
      (node (ref "IC8") (pin "5") (pinfunction "XTAL1_5") (pintype "bidirectional"))
      (node (ref "Q3") (pin "2") (pinfunction "2_2") (pintype "passive"))
      (node (ref "R64") (pin "1") (pinfunction "1_1") (pintype "passive"))
    )
    (net (code "39") (name "Net-(IC8-XTAL2)") (class "Default")
      (node (ref "C59") (pin "1") (pinfunction "1_1") (pintype "passive"))
      (node (ref "IC8") (pin "4") (pinfunction "XTAL2_4") (pintype "bidirectional"))
      (node (ref "Q3") (pin "1") (pinfunction "1_1") (pintype "passive"))
      (node (ref "R64") (pin "2") (pinfunction "2_2") (pintype "passive"))
    )
    (net (code "40") (name "Net-(JP1-Pad2)") (class "Default")
      (node (ref "JP1") (pin "2") (pinfunction "2_2") (pintype "passive"))
      (node (ref "R18") (pin "1") (pinfunction "1_1") (pintype "passive"))
    )
    (net (code "41") (name "Net-(JP1-Pad4)") (class "Default")
      (node (ref "JP1") (pin "4") (pinfunction "4_4") (pintype "passive"))
      (node (ref "R2") (pin "1") (pinfunction "1_1") (pintype "passive"))
    )
    (net (code "42") (name "Net-(JP1-Pad6)") (class "Default")
      (node (ref "JP1") (pin "6") (pinfunction "6_6") (pintype "passive"))
      (node (ref "R6") (pin "1") (pinfunction "1_1") (pintype "passive"))
    )
    (net (code "43") (name "Net-(JP1-Pad8)") (class "Default")
      (node (ref "JP1") (pin "8") (pinfunction "8_8") (pintype "passive"))
      (node (ref "R16") (pin "1") (pinfunction "1_1") (pintype "passive"))
    )
    (net (code "44") (name "Net-(L1-Pad2)") (class "Default")
      (node (ref "L1") (pin "2") (pinfunction "2_2") (pintype "passive"))
      (node (ref "R20") (pin "2") (pinfunction "2_2") (pintype "passive"))
    )
    (net (code "45") (name "Net-(L2-Pad2)") (class "Default")
      (node (ref "L2") (pin "2") (pinfunction "2_2") (pintype "passive"))
      (node (ref "R19") (pin "2") (pinfunction "2_2") (pintype "passive"))
    )
    (net (code "46") (name "Net-(LED1-PadA)") (class "Default")
      (node (ref "LED1") (pin "A") (pinfunction "A_A") (pintype "passive"))
      (node (ref "R10") (pin "1") (pinfunction "1_1") (pintype "passive"))
    )
    (net (code "47") (name "Net-(LED2-PadA)") (class "Default")
      (node (ref "LED2") (pin "A") (pinfunction "A_A") (pintype "passive"))
      (node (ref "R11") (pin "1") (pinfunction "1_1") (pintype "passive"))
    )
    (net (code "48") (name "Net-(LED3-PadA)") (class "Default")
      (node (ref "LED3") (pin "A") (pinfunction "A_A") (pintype "passive"))
      (node (ref "R12") (pin "1") (pinfunction "1_1") (pintype "passive"))
    )
    (net (code "49") (name "Net-(LED4-PadA)") (class "Default")
      (node (ref "LED4") (pin "A") (pinfunction "A_A") (pintype "passive"))
      (node (ref "R13") (pin "1") (pinfunction "1_1") (pintype "passive"))
    )
    (net (code "50") (name "Net-(LED5-PadA)") (class "Default")
      (node (ref "LED5") (pin "A") (pinfunction "A_A") (pintype "passive"))
      (node (ref "R14") (pin "1") (pinfunction "1_1") (pintype "passive"))
    )
    (net (code "51") (name "Net-(Q1-D-Pad1)") (class "Default")
      (node (ref "Q1") (pin "1") (pinfunction "D_1") (pintype "passive"))
      (node (ref "Q1") (pin "2") (pinfunction "D_2") (pintype "passive"))
      (node (ref "Q1") (pin "5") (pinfunction "D_5") (pintype "passive"))
      (node (ref "Q1") (pin "6") (pinfunction "D_6") (pintype "passive"))
      (node (ref "R7") (pin "2") (pinfunction "2_2") (pintype "passive"))
    )
    (net (code "52") (name "Net-(R50-Pad2)") (class "Default")
      (node (ref "R50") (pin "2") (pinfunction "2_2") (pintype "passive"))
      (node (ref "RJ1") (pin "Y-") (pinfunction "Y-_Y-") (pintype "bidirectional"))
    )
    (net (code "53") (name "Net-(R61-Pad2)") (class "Default")
      (node (ref "R61") (pin "2") (pinfunction "2_2") (pintype "passive"))
      (node (ref "RJ1") (pin "G-") (pinfunction "G-_G-") (pintype "bidirectional"))
      (node (ref "RJ1") (pin "G--") (pinfunction "G-_G--") (pintype "bidirectional"))
    )
    (net (code "54") (name "Net-(SJ1-Pad2)") (class "Default")
      (node (ref "SJ1") (pin "2") (pinfunction "2_2") (pintype "passive"))
      (node (ref "U1") (pin "AREF") (pinfunction "AREF_AREF") (pintype "bidirectional"))
    )
    (net (code "55") (name "Net-(X2-D_N)") (class "Default")
      (node (ref "R9") (pin "1") (pinfunction "1_1") (pintype "passive"))
      (node (ref "X2") (pin "2") (pinfunction "D_N_2") (pintype "bidirectional"))
    )
    (net (code "56") (name "Net-(X2-D_P)") (class "Default")
      (node (ref "R8") (pin "1") (pinfunction "1_1") (pintype "passive"))
      (node (ref "X2") (pin "3") (pinfunction "D_P_3") (pintype "bidirectional"))
    )
    (net (code "57") (name "P0[0]") (class "Default")
      (node (ref "IC1") (pin "46") (pinfunction "P0[0]/RD1/TXD3/SDA1_46") (pintype "bidirectional"))
      (node (ref "U1") (pin "10") (pinfunction "10_10") (pintype "bidirectional"))
      (node (ref "U1") (pin "23") (pinfunction "23_23") (pintype "bidirectional"))
    )
    (net (code "58") (name "P0[1]") (class "Default")
      (node (ref "IC1") (pin "47") (pinfunction "P0[1]/TD1/RXD3/SCL1_47") (pintype "bidirectional"))
      (node (ref "U1") (pin "48") (pinfunction "48_48") (pintype "bidirectional"))
      (node (ref "U1") (pin "49") (pinfunction "49_49") (pintype "bidirectional"))
    )
    (net (code "59") (name "P0[4]") (class "Default")
      (node (ref "IC1") (pin "81") (pinfunction "P0[4]/I2SRX_CLK/RD2/CAP2[0]_81") (pintype "bidirectional"))
      (node (ref "U1") (pin "8") (pinfunction "8_8") (pintype "bidirectional"))
    )
    (net (code "60") (name "P0[5]") (class "Default")
      (node (ref "IC1") (pin "80") (pinfunction "P0[5]/I2SRX_WS/TD2/CAP2[1]_80") (pintype "bidirectional"))
      (node (ref "U1") (pin "7") (pinfunction "7_7") (pintype "bidirectional"))
    )
    (net (code "61") (name "P0[10]") (class "Default")
      (node (ref "IC1") (pin "48") (pinfunction "P0[10]/TXD2/SDA2/MAT3[0]_48") (pintype "bidirectional"))
      (node (ref "U1") (pin "42") (pinfunction "42_42") (pintype "bidirectional"))
      (node (ref "U1") (pin "46") (pinfunction "46_46") (pintype "bidirectional"))
    )
    (net (code "62") (name "P0[11]") (class "Default")
      (node (ref "IC1") (pin "49") (pinfunction "P0[11]/RXD2/SCL2/MAT3[1]_49") (pintype "bidirectional"))
      (node (ref "U1") (pin "38") (pinfunction "38_38") (pintype "bidirectional"))
    )
    (net (code "63") (name "P0[15]") (class "Default")
      (node (ref "IC1") (pin "62") (pinfunction "P0[15]/TXD1/SCK0/SCK_62") (pintype "bidirectional"))
      (node (ref "U1") (pin "52") (pinfunction "52_52") (pintype "bidirectional"))
    )
    (net (code "64") (name "P0[16]") (class "Default")
      (node (ref "IC1") (pin "63") (pinfunction "P0[16]/RXD1/SSEL0/SSEL_63") (pintype "bidirectional"))
      (node (ref "U1") (pin "44") (pinfunction "44_44") (pintype "bidirectional"))
    )
    (net (code "65") (name "P0[17]") (class "Default")
      (node (ref "IC1") (pin "61") (pinfunction "P0[17]/CTS1/MISO0/MISO_61") (pintype "bidirectional"))
      (node (ref "U1") (pin "50") (pinfunction "50_50") (pintype "bidirectional"))
    )
    (net (code "66") (name "P0[18]") (class "Default")
      (node (ref "IC1") (pin "60") (pinfunction "P0[18]/DCD1/MOSI0/MOSI_60") (pintype "bidirectional"))
      (node (ref "U1") (pin "51") (pinfunction "51_51") (pintype "bidirectional"))
    )
    (net (code "67") (name "P0[19]") (class "Default")
      (node (ref "IC1") (pin "59") (pinfunction "P0[19]/DSR1/SDA1_59") (pintype "bidirectional"))
      (node (ref "U1") (pin "22") (pinfunction "22_22") (pintype "bidirectional"))
    )
    (net (code "68") (name "P0[20]") (class "Default")
      (node (ref "IC1") (pin "58") (pinfunction "P0[20]/DTR1/SCL1_58") (pintype "bidirectional"))
      (node (ref "U1") (pin "24") (pinfunction "24_24") (pintype "bidirectional"))
    )
    (net (code "69") (name "P0[21]") (class "Default")
      (node (ref "IC1") (pin "57") (pinfunction "P0[21]/RI1/RD1_57") (pintype "bidirectional"))
      (node (ref "U1") (pin "26") (pinfunction "26_26") (pintype "bidirectional"))
    )
    (net (code "70") (name "P0[22]") (class "Default")
      (node (ref "IC1") (pin "56") (pinfunction "P0[22]/RTS1/TD1_56") (pintype "bidirectional"))
      (node (ref "U1") (pin "28") (pinfunction "28_28") (pintype "bidirectional"))
    )
    (net (code "71") (name "P0[23]") (class "Default")
      (node (ref "IC1") (pin "9") (pinfunction "P0[23]/AD0[0]/I2SRX_CLK/CAP3[0]_9") (pintype "bidirectional"))
      (node (ref "U1") (pin "A8") (pinfunction "A8_A8") (pintype "bidirectional"))
    )
    (net (code "72") (name "P0[24]") (class "Default")
      (node (ref "IC1") (pin "8") (pinfunction "P0[24]/AD0[1]/I2SRX_WS/CAP3[1]_8") (pintype "bidirectional"))
      (node (ref "U1") (pin "A1") (pinfunction "A1(TX0)_A1") (pintype "bidirectional"))
    )
    (net (code "73") (name "P0[25]") (class "Default")
      (node (ref "C24") (pin "2") (pinfunction "2_2") (pintype "passive"))
      (node (ref "IC1") (pin "7") (pinfunction "P0[25]/AD0[2]/I2SRX_SDA/TXD3_7") (pintype "bidirectional"))
      (node (ref "R1") (pin "1") (pinfunction "1_1") (pintype "passive"))
      (node (ref "R2") (pin "2") (pinfunction "2_2") (pintype "passive"))
    )
    (net (code "74") (name "P0[26]") (class "Default")
      (node (ref "C23") (pin "2") (pinfunction "2_2") (pintype "passive"))
      (node (ref "IC1") (pin "6") (pinfunction "P0[26]/AD0[3]/AOUT/RXD3_6") (pintype "bidirectional"))
      (node (ref "R3") (pin "1") (pinfunction "1_1") (pintype "passive"))
      (node (ref "R6") (pin "2") (pinfunction "2_2") (pintype "passive"))
    )
    (net (code "75") (name "P1[18]") (class "Default")
      (node (ref "IC1") (pin "32") (pinfunction "P1[18]/USB_UP_LED/PWM1[1]/CAP1[0]_32") (pintype "bidirectional"))
      (node (ref "R10") (pin "2") (pinfunction "2_2") (pintype "passive"))
    )
    (net (code "76") (name "P1[19]") (class "Default")
      (node (ref "IC1") (pin "33") (pinfunction "P1[19]/MC0A/USB_PPWR/CAP1[1]_33") (pintype "bidirectional"))
      (node (ref "R11") (pin "2") (pinfunction "2_2") (pintype "passive"))
    )
    (net (code "77") (name "P1[20]") (class "Default")
      (node (ref "IC1") (pin "34") (pinfunction "P1[20]/MCFB0/PWM1[2]/SCK0_34") (pintype "bidirectional"))
      (node (ref "R12") (pin "2") (pinfunction "2_2") (pintype "passive"))
    )
    (net (code "78") (name "P1[21]") (class "Default")
      (node (ref "IC1") (pin "35") (pinfunction "P1[21]/MCABORT/PWM1[3]/SSEL0_35") (pintype "bidirectional"))
      (node (ref "R13") (pin "2") (pinfunction "2_2") (pintype "passive"))
    )
    (net (code "79") (name "P1[22]") (class "Default")
      (node (ref "IC1") (pin "36") (pinfunction "P1[22]/MC0B/USB_PWRD/MAT1[0]_36") (pintype "bidirectional"))
      (node (ref "U1") (pin "A9") (pinfunction "A9_A9") (pintype "bidirectional"))
    )
    (net (code "80") (name "P1[23]") (class "Default")
      (node (ref "IC1") (pin "37") (pinfunction "P1[23]/MCFB1/PWM1[4]/MISO0_37") (pintype "bidirectional"))
      (node (ref "U1") (pin "A10") (pinfunction "A10_A10") (pintype "bidirectional"))
    )
    (net (code "81") (name "P1[24]") (class "Default")
      (node (ref "IC1") (pin "38") (pinfunction "P1[24]/MCFB2/PWM1[5]/MOSI0_38") (pintype "bidirectional"))
      (node (ref "U1") (pin "A2") (pinfunction "A2_A2") (pintype "bidirectional"))
    )
    (net (code "82") (name "P1[25]") (class "Default")
      (node (ref "IC1") (pin "39") (pinfunction "P1[25]/MC1A/MAT1[1]_39") (pintype "bidirectional"))
      (node (ref "U1") (pin "A11") (pinfunction "A11_A11") (pintype "bidirectional"))
    )
    (net (code "83") (name "P1[26]") (class "Default")
      (node (ref "IC1") (pin "40") (pinfunction "P1[26]/MC1B/PWM1[6]/CAP0[0]_40") (pintype "bidirectional"))
      (node (ref "U1") (pin "A6") (pinfunction "A6_A6") (pintype "bidirectional"))
    )
    (net (code "84") (name "P1[27]") (class "Default")
      (node (ref "IC1") (pin "43") (pinfunction "P1[27]/CLKOUT/USB_OVRCR/CAP0[1]_43") (pintype "bidirectional"))
      (node (ref "U1") (pin "A7") (pinfunction "A7_A7") (pintype "bidirectional"))
    )
    (net (code "85") (name "P1[28]") (class "Default")
      (node (ref "IC1") (pin "44") (pinfunction "P1[28]/MC2A/PCAP1[0]/MAT0[0]_44") (pintype "bidirectional"))
      (node (ref "U1") (pin "11") (pinfunction "11_11") (pintype "bidirectional"))
      (node (ref "U1") (pin "25") (pinfunction "25_25") (pintype "bidirectional"))
    )
    (net (code "86") (name "P1[29]") (class "Default")
      (node (ref "IC1") (pin "45") (pinfunction "P1[29]/MC2B/PCAP1[1]/MAT0[1]_45") (pintype "bidirectional"))
      (node (ref "U1") (pin "27") (pinfunction "27_27") (pintype "bidirectional"))
      (node (ref "U1") (pin "32") (pinfunction "32_32") (pintype "bidirectional"))
    )
    (net (code "87") (name "P1[30]") (class "Default")
      (node (ref "C22") (pin "2") (pinfunction "2_2") (pintype "passive"))
      (node (ref "IC1") (pin "21") (pinfunction "P1[30]/VBUS/AD0[4]_21") (pintype "bidirectional"))
      (node (ref "R15") (pin "1") (pinfunction "1_1") (pintype "passive"))
      (node (ref "R16") (pin "2") (pinfunction "2_2") (pintype "passive"))
    )
    (net (code "88") (name "P1[31]") (class "Default")
      (node (ref "C21") (pin "1") (pinfunction "1_1") (pintype "passive"))
      (node (ref "IC1") (pin "20") (pinfunction "P1[31]/SCK1/AD0[5]_20") (pintype "bidirectional"))
      (node (ref "R17") (pin "1") (pinfunction "1_1") (pintype "passive"))
      (node (ref "R18") (pin "2") (pinfunction "2_2") (pintype "passive"))
    )
    (net (code "89") (name "P2[0]") (class "Default")
      (node (ref "IC1") (pin "75") (pinfunction "P2[0]/PWM1[1]/TXD1_75") (pintype "bidirectional"))
      (node (ref "U1") (pin "6") (pinfunction "6_6") (pintype "bidirectional"))
    )
    (net (code "90") (name "P2[1]") (class "Default")
      (node (ref "IC1") (pin "74") (pinfunction "P2[1]/PWM1[2]/RXD1_74") (pintype "bidirectional"))
      (node (ref "U1") (pin "3") (pinfunction "3_3") (pintype "bidirectional"))
      (node (ref "U1") (pin "5") (pinfunction "5_5") (pintype "bidirectional"))
    )
    (net (code "91") (name "P2[2]") (class "Default")
      (node (ref "IC1") (pin "73") (pinfunction "P2[2]/PWM1[3]/CTS1/TRACEDATA[3]_73") (pintype "bidirectional"))
      (node (ref "U1") (pin "4") (pinfunction "4_4") (pintype "bidirectional"))
    )
    (net (code "92") (name "P2[3]") (class "Default")
      (node (ref "IC1") (pin "70") (pinfunction "P2[3]/PWM1[4]/DCD1/TRACEDATA[2]_70") (pintype "bidirectional"))
      (node (ref "U1") (pin "2") (pinfunction "2_2") (pintype "bidirectional"))
    )
    (net (code "93") (name "P2[4]") (class "Default")
      (node (ref "IC1") (pin "69") (pinfunction "P2[4]/PWM1[5]/DSR1/TRACEDATA[1]_69") (pintype "bidirectional"))
      (node (ref "U1") (pin "13") (pinfunction "13_13") (pintype "bidirectional"))
    )
    (net (code "94") (name "P2[5]") (class "Default")
      (node (ref "IC1") (pin "68") (pinfunction "P2[5]/PWM1[6]/DTR1/TRACEDATA[0]_68") (pintype "bidirectional"))
      (node (ref "U1") (pin "14") (pinfunction "14(TX3)_14") (pintype "bidirectional"))
    )
    (net (code "95") (name "P2[6]") (class "Default")
      (node (ref "IC1") (pin "67") (pinfunction "P2[6]/PCAP1[0]/RI1/TRACECLK_67") (pintype "bidirectional"))
      (node (ref "U1") (pin "15") (pinfunction "15(RX3)_15") (pintype "bidirectional"))
    )
    (net (code "96") (name "P2[7]") (class "Default")
      (node (ref "IC1") (pin "66") (pinfunction "P2[7]/RD2/RTS1_66") (pintype "bidirectional"))
      (node (ref "U1") (pin "18") (pinfunction "18(TX1)_18") (pintype "bidirectional"))
    )
    (net (code "97") (name "P2[8]") (class "Default")
      (node (ref "IC1") (pin "65") (pinfunction "P2[8]/TD2/TXD2_65") (pintype "bidirectional"))
      (node (ref "U1") (pin "19") (pinfunction "19(RX1)_19") (pintype "bidirectional"))
    )
    (net (code "98") (name "P2[10]") (class "Default")
      (node (ref "IC1") (pin "53") (pinfunction "P2[10]/EINT0/NMI_53") (pintype "bidirectional"))
      (node (ref "ISP") (pin "3") (pinfunction "I_3") (pintype "passive"))
      (node (ref "ISP") (pin "4") (pinfunction "I_4") (pintype "passive"))
      (node (ref "R5") (pin "1") (pinfunction "1_1") (pintype "passive"))
      (node (ref "U1") (pin "40") (pinfunction "40_40") (pintype "bidirectional"))
      (node (ref "U1") (pin "47") (pinfunction "47_47") (pintype "bidirectional"))
    )
    (net (code "99") (name "P2[11]") (class "Default")
      (node (ref "IC1") (pin "52") (pinfunction "P2[11]/EINT1/I2STX_CLK_52") (pintype "bidirectional"))
      (node (ref "U1") (pin "30") (pinfunction "30_30") (pintype "bidirectional"))
    )
    (net (code "100") (name "P2[12]") (class "Default")
      (node (ref "DFU") (pin "3") (pinfunction "I_3") (pintype "passive"))
      (node (ref "DFU") (pin "4") (pinfunction "I_4") (pintype "passive"))
      (node (ref "IC1") (pin "51") (pinfunction "P2[12]/EINT2/I2STX_WS_51") (pintype "bidirectional"))
      (node (ref "U1") (pin "34") (pinfunction "34_34") (pintype "bidirectional"))
    )
    (net (code "101") (name "P2[13]") (class "Default")
      (node (ref "IC1") (pin "50") (pinfunction "P2[13]/EINT3/I2STX_SDA_50") (pintype "bidirectional"))
      (node (ref "U1") (pin "36") (pinfunction "36_36") (pintype "bidirectional"))
    )
    (net (code "102") (name "P3[25]") (class "Default")
      (node (ref "IC1") (pin "27") (pinfunction "P3[25]/MAT0[0]/PWM1[2]_27") (pintype "bidirectional"))
      (node (ref "U1") (pin "A3") (pinfunction "A3_A3") (pintype "bidirectional"))
    )
    (net (code "103") (name "P3[26]") (class "Default")
      (node (ref "IC1") (pin "26") (pinfunction "P3[26]/STCLK/MAT0[1]/PWM1[3]_26") (pintype "bidirectional"))
      (node (ref "U1") (pin "A0") (pinfunction "A0(RX0)_A0") (pintype "bidirectional"))
    )
    (net (code "104") (name "P4[28]") (class "Default")
      (node (ref "IC1") (pin "82") (pinfunction "P4[28]/RX_MCLK/MAT2[0]/TXD3_82") (pintype "bidirectional"))
      (node (ref "U1") (pin "9") (pinfunction "9_9") (pintype "bidirectional"))
    )
    (net (code "105") (name "P4[29]") (class "Default")
      (node (ref "IC1") (pin "85") (pinfunction "P4[29]/TX_MCLK/MAT2[1]/RXD3_85") (pintype "bidirectional"))
      (node (ref "U1") (pin "12") (pinfunction "12_12") (pintype "bidirectional"))
    )
    (net (code "106") (name "RD+") (class "Default")
      (node (ref "C56") (pin "1") (pinfunction "1_1") (pintype "passive"))
      (node (ref "IC8") (pin "23") (pinfunction "RX+_23") (pintype "bidirectional"))
      (node (ref "R56") (pin "2") (pinfunction "2_2") (pintype "passive"))
      (node (ref "RJ1") (pin "RD+") (pinfunction "RD+_RD+") (pintype "bidirectional"))
    )
    (net (code "107") (name "RD-") (class "Default")
      (node (ref "C57") (pin "1") (pinfunction "1_1") (pintype "passive"))
      (node (ref "IC8") (pin "22") (pinfunction "RX-_22") (pintype "bidirectional"))
      (node (ref "R57") (pin "2") (pinfunction "2_2") (pintype "passive"))
      (node (ref "RJ1") (pin "RD-") (pinfunction "RD-_RD-") (pintype "bidirectional"))
    )
    (net (code "108") (name "RTCK") (class "Default")
      (node (ref "IC1") (pin "100") (pinfunction "RTCK_100") (pintype "bidirectional"))
      (node (ref "JTAG") (pin "7") (pinfunction "7_7") (pintype "passive"))
    )
    (net (code "109") (name "RX_0") (class "Default")
      (node (ref "FTDI") (pin "4") (pinfunction "4_4") (pintype "passive"))
      (node (ref "IC1") (pin "99") (pinfunction "P0[3]/RXD0/AD0[6]_99") (pintype "bidirectional"))
      (node (ref "U1") (pin "0") (pinfunction "0(RX0)_0") (pintype "bidirectional"))
    )
    (net (code "110") (name "SCL") (class "Default")
      (node (ref "IC1") (pin "24") (pinfunction "P0[28]/SCL0/USB_SCL_24") (pintype "bidirectional"))
      (node (ref "U1") (pin "21") (pinfunction "21(SCL)_21") (pintype "bidirectional"))
      (node (ref "U1") (pin "SCL1") (pinfunction "SCL_SCL1") (pintype "bidirectional"))
    )
    (net (code "111") (name "SDA") (class "Default")
      (node (ref "IC1") (pin "25") (pinfunction "P0[27]/SDA0/USB_SDA_25") (pintype "bidirectional"))
      (node (ref "U1") (pin "20") (pinfunction "20(SDA)_20") (pintype "bidirectional"))
      (node (ref "U1") (pin "SDA1") (pinfunction "SDA_SDA1") (pintype "bidirectional"))
    )
    (net (code "112") (name "SD_CS") (class "Default")
      (node (ref "IC1") (pin "79") (pinfunction "P0[6]/I2SRX_SDA/SSEL1/MAT2[0]_79") (pintype "bidirectional"))
      (node (ref "U2") (pin "2") (pinfunction "CS_2") (pintype "bidirectional"))
    )
    (net (code "113") (name "SD_MISO") (class "Default")
      (node (ref "IC1") (pin "77") (pinfunction "P0[8]/I2STX_WS/MISO1/MAT2[2]_77") (pintype "bidirectional"))
      (node (ref "U1") (pin "MISO") (pinfunction "MISO_MISO") (pintype "bidirectional"))
      (node (ref "U2") (pin "7") (pinfunction "DO_7") (pintype "bidirectional"))
    )
    (net (code "114") (name "SD_MOSI") (class "Default")
      (node (ref "IC1") (pin "76") (pinfunction "P0[9]/I2STX_SDA/MOSI1/MAT2[3]_76") (pintype "bidirectional"))
      (node (ref "U1") (pin "MOSI") (pinfunction "MOSI_MOSI") (pintype "bidirectional"))
      (node (ref "U2") (pin "3") (pinfunction "DI_3") (pintype "bidirectional"))
    )
    (net (code "115") (name "SD_SCK") (class "Default")
      (node (ref "IC1") (pin "78") (pinfunction "P0[7]/I2STX_CLK/SCK1/MAT2[1]_78") (pintype "bidirectional"))
      (node (ref "U1") (pin "SCK") (pinfunction "SCK_SCK") (pintype "bidirectional"))
      (node (ref "U2") (pin "5") (pinfunction "SCK_5") (pintype "bidirectional"))
    )
    (net (code "116") (name "TCK-SWDCLK") (class "Default")
      (node (ref "IC1") (pin "5") (pinfunction "TCK/SWDCLK_5") (pintype "bidirectional"))
      (node (ref "JTAG") (pin "4") (pinfunction "4_4") (pintype "passive"))
    )
    (net (code "117") (name "TD+") (class "Default")
      (node (ref "C54") (pin "1") (pinfunction "1_1") (pintype "passive"))
      (node (ref "IC8") (pin "21") (pinfunction "TX+_21") (pintype "bidirectional"))
      (node (ref "R54") (pin "2") (pinfunction "2_2") (pintype "passive"))
      (node (ref "RJ1") (pin "TD+") (pinfunction "TD+_TD+") (pintype "bidirectional"))
    )
    (net (code "118") (name "TD-") (class "Default")
      (node (ref "C55") (pin "1") (pinfunction "1_1") (pintype "passive"))
      (node (ref "IC8") (pin "20") (pinfunction "TX-_20") (pintype "bidirectional"))
      (node (ref "R55") (pin "2") (pinfunction "2_2") (pintype "passive"))
      (node (ref "RJ1") (pin "TD-") (pinfunction "TD-_TD-") (pintype "bidirectional"))
    )
    (net (code "119") (name "TDI") (class "Default")
      (node (ref "IC1") (pin "2") (pinfunction "TDI_2") (pintype "bidirectional"))
      (node (ref "JTAG") (pin "8") (pinfunction "8_8") (pintype "passive"))
    )
    (net (code "120") (name "TDO-SWO") (class "Default")
      (node (ref "IC1") (pin "1") (pinfunction "TDO/SWO_1") (pintype "bidirectional"))
      (node (ref "JTAG") (pin "6") (pinfunction "6_6") (pintype "passive"))
    )
    (net (code "121") (name "TMS-SWDIO") (class "Default")
      (node (ref "IC1") (pin "3") (pinfunction "TMS/SWDIO_3") (pintype "bidirectional"))
      (node (ref "JTAG") (pin "2") (pinfunction "2_2") (pintype "passive"))
    )
    (net (code "122") (name "TX_0") (class "Default")
      (node (ref "FTDI") (pin "5") (pinfunction "5_5") (pintype "passive"))
      (node (ref "IC1") (pin "98") (pinfunction "P0[2]/TXD0/AD0[7]_98") (pintype "bidirectional"))
      (node (ref "U1") (pin "1") (pinfunction "1(TX0)_1") (pintype "bidirectional"))
    )
    (net (code "123") (name "USB_CONNECT") (class "Default")
      (node (ref "IC1") (pin "64") (pinfunction "P2[9]/USB_CONNECT/RXD2_64") (pintype "bidirectional"))
      (node (ref "Q1") (pin "3") (pinfunction "G_3") (pintype "passive"))
    )
    (net (code "124") (name "USB_N") (class "Default")
      (node (ref "C4") (pin "2") (pinfunction "2_2") (pintype "passive"))
      (node (ref "IC1") (pin "30") (pinfunction "P0[30]/USB_D-_30") (pintype "bidirectional"))
      (node (ref "R9") (pin "2") (pinfunction "2_2") (pintype "passive"))
    )
    (net (code "125") (name "USB_P") (class "Default")
      (node (ref "C5") (pin "2") (pinfunction "2_2") (pintype "passive"))
      (node (ref "IC1") (pin "29") (pinfunction "P0[29]/USB_D+_29") (pintype "bidirectional"))
      (node (ref "R7") (pin "1") (pinfunction "1_1") (pintype "passive"))
      (node (ref "R8") (pin "2") (pinfunction "2_2") (pintype "passive"))
    )
    (net (code "126") (name "VIN") (class "Default")
      (node (ref "SJ3") (pin "1") (pinfunction "1_1") (pintype "passive"))
      (node (ref "U1") (pin "VIN") (pinfunction "VIN_VIN") (pintype "bidirectional"))
    )
    (net (code "127") (name "VUSB") (class "Default")
      (node (ref "D1") (pin "A") (pinfunction "A_A") (pintype "passive"))
      (node (ref "X2") (pin "1") (pinfunction "VCC_1") (pintype "bidirectional"))
    )
    (net (code "128") (name "unconnected-(FTDI-Pad2)") (class "Default")
      (node (ref "FTDI") (pin "2") (pinfunction "2_2") (pintype "passive"))
    )
    (net (code "129") (name "unconnected-(FTDI-Pad3)") (class "Default")
      (node (ref "FTDI") (pin "3") (pinfunction "3_3") (pintype "passive"))
    )
    (net (code "130") (name "unconnected-(FTDI-Pad6)") (class "Default")
      (node (ref "FTDI") (pin "6") (pinfunction "6_6") (pintype "passive"))
    )
    (net (code "131") (name "unconnected-(IC1-RTCX1-Pad16)") (class "Default")
      (node (ref "IC1") (pin "16") (pinfunction "RTCX1_16") (pintype "bidirectional"))
    )
    (net (code "132") (name "unconnected-(IC1-RTCX2-Pad18)") (class "Default")
      (node (ref "IC1") (pin "18") (pinfunction "RTCX2_18") (pintype "bidirectional"))
    )
    (net (code "133") (name "unconnected-(IC1-TRST-Pad4)") (class "Default")
      (node (ref "IC1") (pin "4") (pinfunction "TRST_4") (pintype "bidirectional"))
    )
    (net (code "134") (name "unconnected-(IC7-NC-Pad1)") (class "Default")
      (node (ref "IC7") (pin "1") (pinfunction "NC_1") (pintype "no_connect"))
    )
    (net (code "135") (name "unconnected-(RJ1-PadNC)") (class "Default")
      (node (ref "RJ1") (pin "NC") (pinfunction "NC_NC") (pintype "bidirectional"))
    )
    (net (code "136") (name "unconnected-(U1-16(TX2)-Pad16)") (class "Default")
      (node (ref "U1") (pin "16") (pinfunction "16(TX2)_16") (pintype "bidirectional"))
    )
    (net (code "137") (name "unconnected-(U1-17(RX2)-Pad17)") (class "Default")
      (node (ref "U1") (pin "17") (pinfunction "17(RX2)_17") (pintype "bidirectional"))
    )
    (net (code "138") (name "unconnected-(U1-Pad29)") (class "Default")
      (node (ref "U1") (pin "29") (pinfunction "29_29") (pintype "bidirectional"))
    )
    (net (code "139") (name "unconnected-(U1-Pad31)") (class "Default")
      (node (ref "U1") (pin "31") (pinfunction "31_31") (pintype "bidirectional"))
    )
    (net (code "140") (name "unconnected-(U1-Pad33)") (class "Default")
      (node (ref "U1") (pin "33") (pinfunction "33_33") (pintype "bidirectional"))
    )
    (net (code "141") (name "unconnected-(U1-Pad35)") (class "Default")
      (node (ref "U1") (pin "35") (pinfunction "35_35") (pintype "bidirectional"))
    )
    (net (code "142") (name "unconnected-(U1-Pad37)") (class "Default")
      (node (ref "U1") (pin "37") (pinfunction "37_37") (pintype "bidirectional"))
    )
    (net (code "143") (name "unconnected-(U1-Pad39)") (class "Default")
      (node (ref "U1") (pin "39") (pinfunction "39_39") (pintype "bidirectional"))
    )
    (net (code "144") (name "unconnected-(U1-Pad41)") (class "Default")
      (node (ref "U1") (pin "41") (pinfunction "41_41") (pintype "bidirectional"))
    )
    (net (code "145") (name "unconnected-(U1-Pad43)") (class "Default")
      (node (ref "U1") (pin "43") (pinfunction "43_43") (pintype "bidirectional"))
    )
    (net (code "146") (name "unconnected-(U1-Pad45)") (class "Default")
      (node (ref "U1") (pin "45") (pinfunction "45_45") (pintype "bidirectional"))
    )
    (net (code "147") (name "unconnected-(U1-Pad53)") (class "Default")
      (node (ref "U1") (pin "53") (pinfunction "53_53") (pintype "bidirectional"))
    )
    (net (code "148") (name "unconnected-(U1-PadA4)") (class "Default")
      (node (ref "U1") (pin "A4") (pinfunction "A4_A4") (pintype "bidirectional"))
    )
    (net (code "149") (name "unconnected-(U1-PadA5)") (class "Default")
      (node (ref "U1") (pin "A5") (pinfunction "A5_A5") (pintype "bidirectional"))
    )
    (net (code "150") (name "unconnected-(U2-NC-Pad1)") (class "Default")
      (node (ref "U2") (pin "1") (pinfunction "NC_1") (pintype "bidirectional"))
    )
    (net (code "151") (name "unconnected-(U2-PadCD1)") (class "Default")
      (node (ref "U2") (pin "CD1") (pinfunction "CD1_CD1") (pintype "bidirectional"))
    )
    (net (code "152") (name "unconnected-(U2-PadCD2)") (class "Default")
      (node (ref "U2") (pin "CD2") (pinfunction "CD2_CD2") (pintype "bidirectional"))
    )
    (net (code "153") (name "unconnected-(U2-RSV-Pad8)") (class "Default")
      (node (ref "U2") (pin "8") (pinfunction "RSV_8") (pintype "bidirectional"))
    )
    (net (code "154") (name "unconnected-(X2-ID-Pad4)") (class "Default")
      (node (ref "X2") (pin "4") (pinfunction "ID_4") (pintype "bidirectional"))
    )
    (net (code "155") (name "~{RSTOUT}") (class "Default")
      (node (ref "IC1") (pin "14") (pinfunction "RSTOUT_14") (pintype "bidirectional"))
      (node (ref "IC8") (pin "15") (pinfunction "NRST_15") (pintype "bidirectional"))
    )
    (net (code "156") (name "~{RST}") (class "Default")
      (node (ref "IC1") (pin "17") (pinfunction "RESET_17") (pintype "bidirectional"))
      (node (ref "JTAG") (pin "10") (pinfunction "10_10") (pintype "passive"))
      (node (ref "R4") (pin "1") (pinfunction "1_1") (pintype "passive"))
      (node (ref "RST") (pin "3") (pinfunction "I_3") (pintype "passive"))
      (node (ref "RST") (pin "4") (pinfunction "I_4") (pintype "passive"))
      (node (ref "U1") (pin "RESET") (pinfunction "RESET_RESET") (pintype "bidirectional"))
      (node (ref "U1") (pin "RST") (pinfunction "RESET_RST") (pintype "bidirectional"))
    )
  )
)
